# LED.net
KiCad netlist of a schematic drawn in Altium Designer
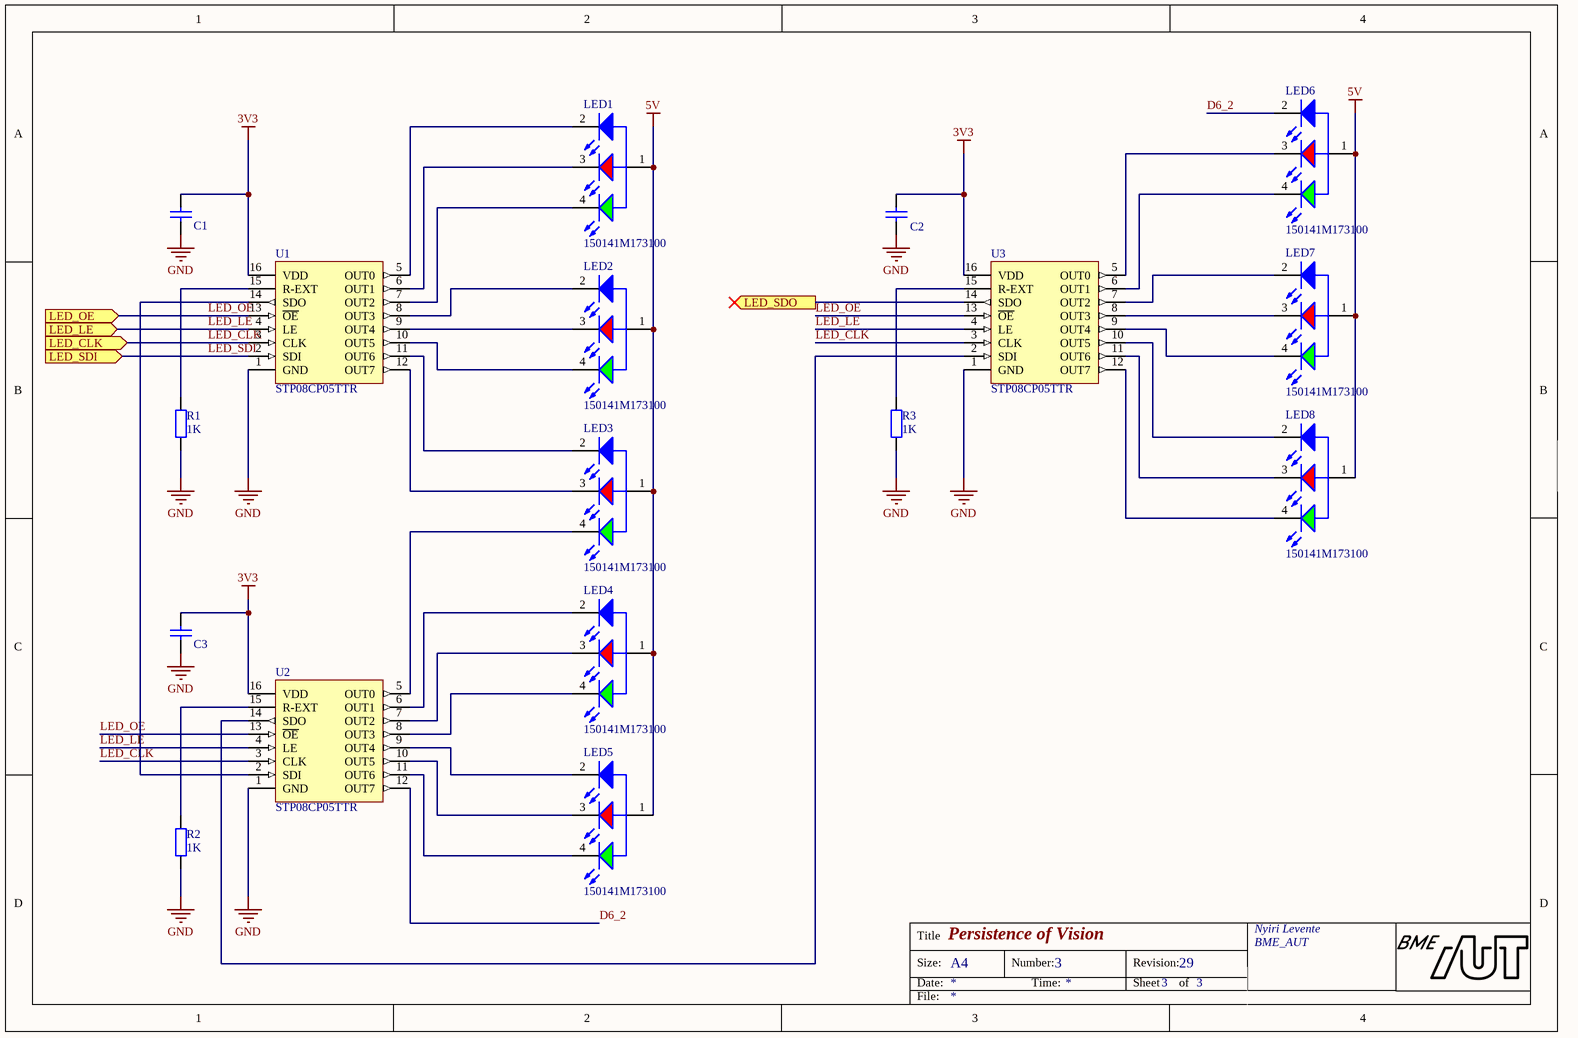
[diagram p0: LED.SchDoc]

(export (version "E")
  (design (tool "Eeschema 10.0.6"))
  (components
    (comp (ref "C1")
      (value "100nF")
      (footprint "FP_0805_CAP_085")
      (description "Capacitor")
      (libsource (lib "hallglib") (part "CAP"))
    )
    (comp (ref "C2")
      (value "100nF")
      (footprint "FP_0805_CAP_085")
      (description "Capacitor")
      (libsource (lib "hallglib") (part "CAP"))
    )
    (comp (ref "C3")
      (value "100nF")
      (footprint "FP_0805_CAP_085")
      (description "Capacitor")
      (libsource (lib "hallglib") (part "CAP"))
    )
    (comp (ref "LED1")
      (value "150141M173100")
      (footprint "SamacSys:150141M173100")
      (description "LED")
      (libsource (lib "hallglib") (part "150141M173100"))
    )
    (comp (ref "LED2")
      (value "150141M173100")
      (footprint "SamacSys:150141M173100")
      (description "LED")
      (libsource (lib "hallglib") (part "150141M173100"))
    )
    (comp (ref "LED3")
      (value "150141M173100")
      (footprint "SamacSys:150141M173100")
      (description "LED")
      (libsource (lib "hallglib") (part "150141M173100"))
    )
    (comp (ref "LED4")
      (value "150141M173100")
      (footprint "SamacSys:150141M173100")
      (description "LED")
      (libsource (lib "hallglib") (part "150141M173100"))
    )
    (comp (ref "LED5")
      (value "150141M173100")
      (footprint "SamacSys:150141M173100")
      (description "LED")
      (libsource (lib "hallglib") (part "150141M173100"))
    )
    (comp (ref "LED6")
      (value "150141M173100")
      (footprint "SamacSys:150141M173100")
      (description "LED")
      (libsource (lib "hallglib") (part "150141M173100"))
    )
    (comp (ref "LED7")
      (value "150141M173100")
      (footprint "SamacSys:150141M173100")
      (description "LED")
      (libsource (lib "hallglib") (part "150141M173100"))
    )
    (comp (ref "LED8")
      (value "150141M173100")
      (footprint "SamacSys:150141M173100")
      (description "LED")
      (libsource (lib "hallglib") (part "150141M173100"))
    )
    (comp (ref "R1")
      (value "1K")
      (footprint "FP_0805_RES")
      (description "Resistor")
      (libsource (lib "hallglib") (part "RES"))
    )
    (comp (ref "R2")
      (value "1K")
      (footprint "FP_0805_RES")
      (description "Resistor")
      (libsource (lib "hallglib") (part "RES"))
    )
    (comp (ref "R3")
      (value "1K")
      (footprint "FP_0805_RES")
      (description "Resistor")
      (libsource (lib "hallglib") (part "RES"))
    )
    (comp (ref "U1")
      (value "STP08CP05TTR")
      (footprint "TSOP65P640X120-16M")
      (description "Low voltage, low current power 8-bit shift register")
      (libsource (lib "hallglib") (part "STP08CP05TTR"))
    )
    (comp (ref "U2")
      (value "STP08CP05TTR")
      (footprint "TSOP65P640X120-16M")
      (description "Low voltage, low current power 8-bit shift register")
      (libsource (lib "hallglib") (part "STP08CP05TTR"))
    )
    (comp (ref "U3")
      (value "STP08CP05TTR")
      (footprint "TSOP65P640X120-16M")
      (description "Low voltage, low current power 8-bit shift register")
      (libsource (lib "hallglib") (part "STP08CP05TTR"))
    )
  )
  (nets
    (net (code "1") (name "/D6_2") (class "Default")
      (node (ref "LED6") (pin "2") (pinfunction "K_2") (pintype "passive"))
      (node (ref "U2") (pin "12") (pinfunction "OUT7_12") (pintype "output"))
    )
    (net (code "2") (name "/LED_CLK") (class "Default")
      (node (ref "U1") (pin "3") (pinfunction "CLK_3") (pintype "input"))
      (node (ref "U2") (pin "3") (pinfunction "CLK_3") (pintype "input"))
      (node (ref "U3") (pin "3") (pinfunction "CLK_3") (pintype "input"))
    )
    (net (code "3") (name "/LED_LE") (class "Default")
      (node (ref "U1") (pin "4") (pinfunction "LE_4") (pintype "input"))
      (node (ref "U2") (pin "4") (pinfunction "LE_4") (pintype "input"))
      (node (ref "U3") (pin "4") (pinfunction "LE_4") (pintype "input"))
    )
    (net (code "4") (name "/LED_OE") (class "Default")
      (node (ref "U1") (pin "13") (pinfunction "~{OE}_13") (pintype "input"))
      (node (ref "U2") (pin "13") (pinfunction "~{OE}_13") (pintype "input"))
      (node (ref "U3") (pin "13") (pinfunction "~{OE}_13") (pintype "input"))
    )
    (net (code "5") (name "/LED_SDI") (class "Default")
      (node (ref "U1") (pin "2") (pinfunction "SDI_2") (pintype "input"))
    )
    (net (code "6") (name "/LED_SDO") (class "Default")
      (node (ref "U3") (pin "14") (pinfunction "SDO_14") (pintype "output"))
    )
    (net (code "7") (name "3V3") (class "Default")
      (node (ref "C1") (pin "2") (pinfunction "2_2") (pintype "passive"))
      (node (ref "C2") (pin "2") (pinfunction "2_2") (pintype "passive"))
      (node (ref "C3") (pin "2") (pinfunction "2_2") (pintype "passive"))
      (node (ref "U1") (pin "16") (pinfunction "VDD_16") (pintype "power_in"))
      (node (ref "U2") (pin "16") (pinfunction "VDD_16") (pintype "power_in"))
      (node (ref "U3") (pin "16") (pinfunction "VDD_16") (pintype "power_in"))
    )
    (net (code "8") (name "5V") (class "Default")
      (node (ref "LED1") (pin "1") (pinfunction "A_1") (pintype "passive"))
      (node (ref "LED2") (pin "1") (pinfunction "A_1") (pintype "passive"))
      (node (ref "LED3") (pin "1") (pinfunction "A_1") (pintype "passive"))
      (node (ref "LED4") (pin "1") (pinfunction "A_1") (pintype "passive"))
      (node (ref "LED5") (pin "1") (pinfunction "A_1") (pintype "passive"))
      (node (ref "LED6") (pin "1") (pinfunction "A_1") (pintype "passive"))
      (node (ref "LED7") (pin "1") (pinfunction "A_1") (pintype "passive"))
      (node (ref "LED8") (pin "1") (pinfunction "A_1") (pintype "passive"))
    )
    (net (code "9") (name "GND") (class "Default")
      (node (ref "C1") (pin "1") (pinfunction "1_1") (pintype "passive"))
      (node (ref "C2") (pin "1") (pinfunction "1_1") (pintype "passive"))
      (node (ref "C3") (pin "1") (pinfunction "1_1") (pintype "passive"))
      (node (ref "R1") (pin "1") (pinfunction "1_1") (pintype "passive"))
      (node (ref "R2") (pin "1") (pinfunction "1_1") (pintype "passive"))
      (node (ref "R3") (pin "1") (pinfunction "1_1") (pintype "passive"))
      (node (ref "U1") (pin "1") (pinfunction "GND_1") (pintype "passive"))
      (node (ref "U2") (pin "1") (pinfunction "GND_1") (pintype "passive"))
      (node (ref "U3") (pin "1") (pinfunction "GND_1") (pintype "passive"))
    )
    (net (code "10") (name "Net-(U1-OUT0)") (class "Default")
      (node (ref "LED1") (pin "2") (pinfunction "K_2") (pintype "passive"))
      (node (ref "U1") (pin "5") (pinfunction "OUT0_5") (pintype "output"))
    )
    (net (code "11") (name "Net-(U1-OUT1)") (class "Default")
      (node (ref "LED1") (pin "3") (pinfunction "K_3") (pintype "passive"))
      (node (ref "U1") (pin "6") (pinfunction "OUT1_6") (pintype "output"))
    )
    (net (code "12") (name "Net-(U1-OUT2)") (class "Default")
      (node (ref "LED1") (pin "4") (pinfunction "K_4") (pintype "passive"))
      (node (ref "U1") (pin "7") (pinfunction "OUT2_7") (pintype "output"))
    )
    (net (code "13") (name "Net-(U1-OUT3)") (class "Default")
      (node (ref "LED2") (pin "2") (pinfunction "K_2") (pintype "passive"))
      (node (ref "U1") (pin "8") (pinfunction "OUT3_8") (pintype "output"))
    )
    (net (code "14") (name "Net-(U1-OUT4)") (class "Default")
      (node (ref "LED2") (pin "3") (pinfunction "K_3") (pintype "passive"))
      (node (ref "U1") (pin "9") (pinfunction "OUT4_9") (pintype "output"))
    )
    (net (code "15") (name "Net-(U1-OUT5)") (class "Default")
      (node (ref "LED2") (pin "4") (pinfunction "K_4") (pintype "passive"))
      (node (ref "U1") (pin "10") (pinfunction "OUT5_10") (pintype "output"))
    )
    (net (code "16") (name "Net-(U1-OUT6)") (class "Default")
      (node (ref "LED3") (pin "2") (pinfunction "K_2") (pintype "passive"))
      (node (ref "U1") (pin "11") (pinfunction "OUT6_11") (pintype "output"))
    )
    (net (code "17") (name "Net-(U1-OUT7)") (class "Default")
      (node (ref "LED3") (pin "3") (pinfunction "K_3") (pintype "passive"))
      (node (ref "U1") (pin "12") (pinfunction "OUT7_12") (pintype "output"))
    )
    (net (code "18") (name "Net-(U1-R-EXT)") (class "Default")
      (node (ref "R1") (pin "2") (pinfunction "2_2") (pintype "passive"))
      (node (ref "U1") (pin "15") (pinfunction "R-EXT_15") (pintype "passive"))
    )
    (net (code "19") (name "Net-(U1-SDO)") (class "Default")
      (node (ref "U1") (pin "14") (pinfunction "SDO_14") (pintype "output"))
      (node (ref "U2") (pin "2") (pinfunction "SDI_2") (pintype "input"))
    )
    (net (code "20") (name "Net-(U2-OUT0)") (class "Default")
      (node (ref "LED3") (pin "4") (pinfunction "K_4") (pintype "passive"))
      (node (ref "U2") (pin "5") (pinfunction "OUT0_5") (pintype "output"))
    )
    (net (code "21") (name "Net-(U2-OUT1)") (class "Default")
      (node (ref "LED4") (pin "2") (pinfunction "K_2") (pintype "passive"))
      (node (ref "U2") (pin "6") (pinfunction "OUT1_6") (pintype "output"))
    )
    (net (code "22") (name "Net-(U2-OUT2)") (class "Default")
      (node (ref "LED4") (pin "3") (pinfunction "K_3") (pintype "passive"))
      (node (ref "U2") (pin "7") (pinfunction "OUT2_7") (pintype "output"))
    )
    (net (code "23") (name "Net-(U2-OUT3)") (class "Default")
      (node (ref "LED4") (pin "4") (pinfunction "K_4") (pintype "passive"))
      (node (ref "U2") (pin "8") (pinfunction "OUT3_8") (pintype "output"))
    )
    (net (code "24") (name "Net-(U2-OUT4)") (class "Default")
      (node (ref "LED5") (pin "2") (pinfunction "K_2") (pintype "passive"))
      (node (ref "U2") (pin "9") (pinfunction "OUT4_9") (pintype "output"))
    )
    (net (code "25") (name "Net-(U2-OUT5)") (class "Default")
      (node (ref "LED5") (pin "3") (pinfunction "K_3") (pintype "passive"))
      (node (ref "U2") (pin "10") (pinfunction "OUT5_10") (pintype "output"))
    )
    (net (code "26") (name "Net-(U2-OUT6)") (class "Default")
      (node (ref "LED5") (pin "4") (pinfunction "K_4") (pintype "passive"))
      (node (ref "U2") (pin "11") (pinfunction "OUT6_11") (pintype "output"))
    )
    (net (code "27") (name "Net-(U2-R-EXT)") (class "Default")
      (node (ref "R2") (pin "2") (pinfunction "2_2") (pintype "passive"))
      (node (ref "U2") (pin "15") (pinfunction "R-EXT_15") (pintype "passive"))
    )
    (net (code "28") (name "Net-(U2-SDO)") (class "Default")
      (node (ref "U2") (pin "14") (pinfunction "SDO_14") (pintype "output"))
      (node (ref "U3") (pin "2") (pinfunction "SDI_2") (pintype "input"))
    )
    (net (code "29") (name "Net-(U3-OUT0)") (class "Default")
      (node (ref "LED6") (pin "3") (pinfunction "K_3") (pintype "passive"))
      (node (ref "U3") (pin "5") (pinfunction "OUT0_5") (pintype "output"))
    )
    (net (code "30") (name "Net-(U3-OUT1)") (class "Default")
      (node (ref "LED6") (pin "4") (pinfunction "K_4") (pintype "passive"))
      (node (ref "U3") (pin "6") (pinfunction "OUT1_6") (pintype "output"))
    )
    (net (code "31") (name "Net-(U3-OUT2)") (class "Default")
      (node (ref "LED7") (pin "2") (pinfunction "K_2") (pintype "passive"))
      (node (ref "U3") (pin "7") (pinfunction "OUT2_7") (pintype "output"))
    )
    (net (code "32") (name "Net-(U3-OUT3)") (class "Default")
      (node (ref "LED7") (pin "3") (pinfunction "K_3") (pintype "passive"))
      (node (ref "U3") (pin "8") (pinfunction "OUT3_8") (pintype "output"))
    )
    (net (code "33") (name "Net-(U3-OUT4)") (class "Default")
      (node (ref "LED7") (pin "4") (pinfunction "K_4") (pintype "passive"))
      (node (ref "U3") (pin "9") (pinfunction "OUT4_9") (pintype "output"))
    )
    (net (code "34") (name "Net-(U3-OUT5)") (class "Default")
      (node (ref "LED8") (pin "2") (pinfunction "K_2") (pintype "passive"))
      (node (ref "U3") (pin "10") (pinfunction "OUT5_10") (pintype "output"))
    )
    (net (code "35") (name "Net-(U3-OUT6)") (class "Default")
      (node (ref "LED8") (pin "3") (pinfunction "K_3") (pintype "passive"))
      (node (ref "U3") (pin "11") (pinfunction "OUT6_11") (pintype "output"))
    )
    (net (code "36") (name "Net-(U3-OUT7)") (class "Default")
      (node (ref "LED8") (pin "4") (pinfunction "K_4") (pintype "passive"))
      (node (ref "U3") (pin "12") (pinfunction "OUT7_12") (pintype "output"))
    )
    (net (code "37") (name "Net-(U3-R-EXT)") (class "Default")
      (node (ref "R3") (pin "2") (pinfunction "2_2") (pintype "passive"))
      (node (ref "U3") (pin "15") (pinfunction "R-EXT_15") (pintype "passive"))
    )
  )
)
